# TopLevel.net
KiCad netlist of a schematic drawn in Altium Designer
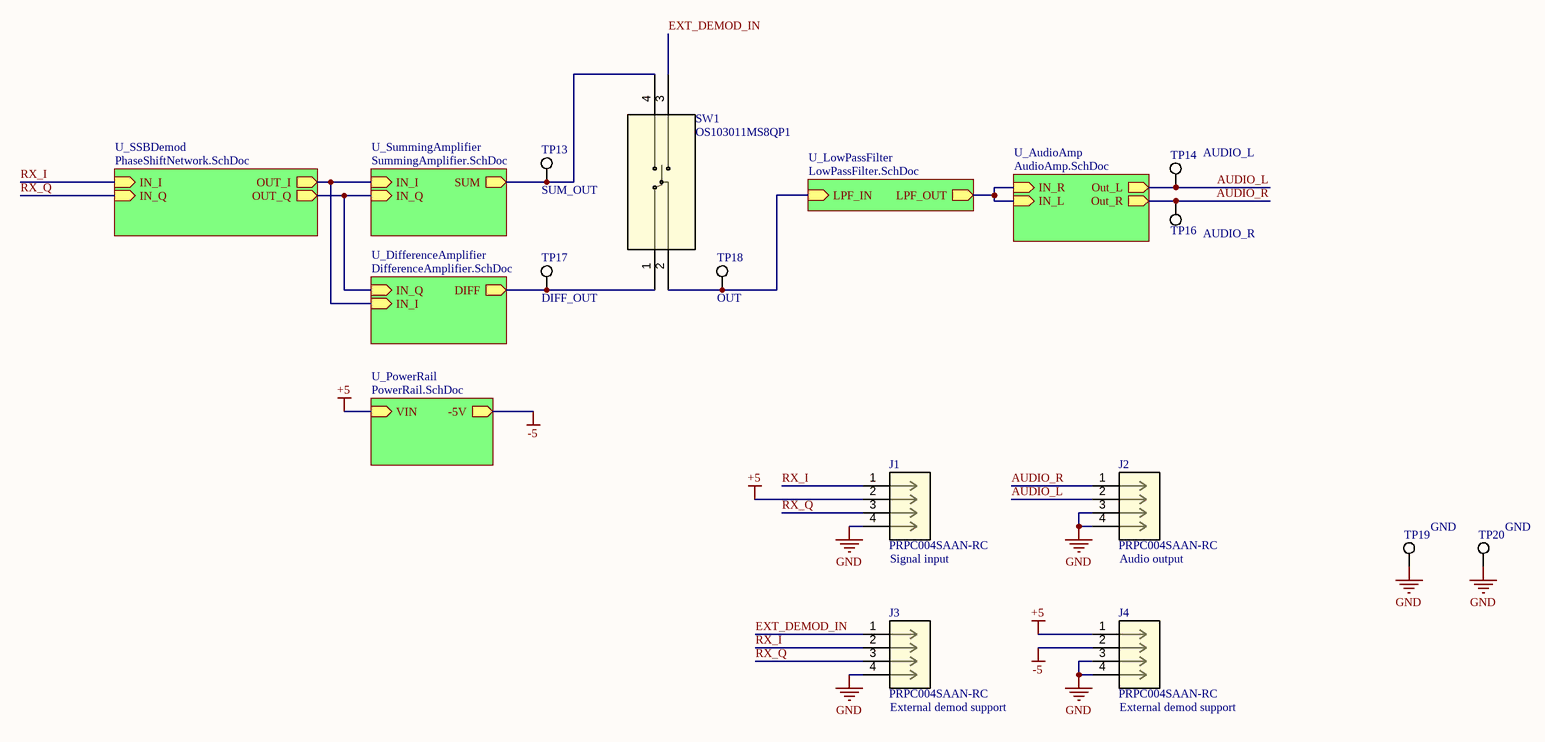
[diagram p0: TopLevel.SchDoc]

(export (version "E")
  (design (tool "Eeschema 10.0.6"))
  (components
    (comp (ref "J1")
      (value "PRPC004SAAN-RC")
      (footprint "CONN4_PRPC004_SUL")
      (description "No Description Available")
      (libsource (lib "PRPC004SAAN-RC") (part "PRPC004SAAN-RC"))
    )
    (comp (ref "J2")
      (value "PRPC004SAAN-RC")
      (footprint "CONN4_PRPC004_SUL")
      (description "No Description Available")
      (libsource (lib "PRPC004SAAN-RC") (part "PRPC004SAAN-RC"))
    )
    (comp (ref "J3")
      (value "PRPC004SAAN-RC")
      (footprint "CONN4_PRPC004_SUL")
      (description "No Description Available")
      (libsource (lib "PRPC004SAAN-RC") (part "PRPC004SAAN-RC"))
    )
    (comp (ref "J4")
      (value "PRPC004SAAN-RC")
      (footprint "CONN4_PRPC004_SUL")
      (description "No Description Available")
      (libsource (lib "PRPC004SAAN-RC") (part "PRPC004SAAN-RC"))
    )
    (comp (ref "SW1")
      (value "OS103011MS8QP1")
      (footprint "DIP4_SP3T-TOP_4P3X8P6_CNK")
      (description "No Description Available")
      (libsource (lib "OS103011MS8QP1") (part "OS103011MS8QP1"))
    )
    (comp (ref "TP13")
      (value "SUM_OUT")
      (footprint "KSTN-5019_V")
      (description "Test Point, 1 Position SMD, RoHS, Tape and Reel")
      (libsource (lib "Altium Content Vault") (part "TESTPOINT_WHITE"))
    )
    (comp (ref "TP14")
      (value "AUDIO_L")
      (footprint "KSTN-5019_V")
      (description "Test Point, 1 Position SMD, RoHS, Tape and Reel")
      (libsource (lib "Altium Content Vault") (part "TESTPOINT_WHITE"))
    )
    (comp (ref "TP16")
      (value "AUDIO_R")
      (footprint "KSTN-5019_V")
      (description "Test Point, 1 Position SMD, RoHS, Tape and Reel")
      (libsource (lib "Altium Content Vault") (part "TESTPOINT_WHITE"))
    )
    (comp (ref "TP17")
      (value "DIFF_OUT")
      (footprint "KSTN-5019_V")
      (description "Test Point, 1 Position SMD, RoHS, Tape and Reel")
      (libsource (lib "Altium Content Vault") (part "TESTPOINT_WHITE"))
    )
    (comp (ref "TP18")
      (value "OUT")
      (footprint "KSTN-5019_V")
      (description "Test Point, 1 Position SMD, RoHS, Tape and Reel")
      (libsource (lib "Altium Content Vault") (part "TESTPOINT_WHITE"))
    )
    (comp (ref "TP19")
      (value "GND")
      (footprint "KSTN-5019_V")
      (description "Test Point, 1 Position SMD, RoHS, Tape and Reel")
      (libsource (lib "Altium Content Vault") (part "TESTPOINT_WHITE"))
    )
    (comp (ref "TP20")
      (value "GND")
      (footprint "KSTN-5019_V")
      (description "Test Point, 1 Position SMD, RoHS, Tape and Reel")
      (libsource (lib "Altium Content Vault") (part "TESTPOINT_WHITE"))
    )
  )
  (nets
    (net (code "1") (name "+5") (class "Default")
      (node (ref "J1") (pin "2") (pinfunction "2_2") (pintype "passive"))
      (node (ref "J4") (pin "1") (pinfunction "1_1") (pintype "passive"))
    )
    (net (code "2") (name "-5") (class "Default")
      (node (ref "J4") (pin "2") (pinfunction "2_2") (pintype "passive"))
    )
    (net (code "3") (name "/AUDIO_L") (class "Default")
      (node (ref "J2") (pin "2") (pinfunction "2_2") (pintype "passive"))
      (node (ref "TP14") (pin "1") (pinfunction "1_1") (pintype "passive"))
    )
    (net (code "4") (name "/AUDIO_R") (class "Default")
      (node (ref "J2") (pin "1") (pinfunction "1_1") (pintype "passive"))
      (node (ref "TP16") (pin "1") (pinfunction "1_1") (pintype "passive"))
    )
    (net (code "5") (name "/DIFF") (class "Default")
      (node (ref "SW1") (pin "1") (pinfunction "1_1") (pintype "passive"))
      (node (ref "TP17") (pin "1") (pinfunction "1_1") (pintype "passive"))
    )
    (net (code "6") (name "/EXT_DEMOD_IN") (class "Default")
      (node (ref "J3") (pin "1") (pinfunction "1_1") (pintype "passive"))
      (node (ref "SW1") (pin "3") (pinfunction "3_3") (pintype "passive"))
    )
    (net (code "7") (name "/LPF_IN") (class "Default")
      (node (ref "SW1") (pin "2") (pinfunction "2_2") (pintype "passive"))
      (node (ref "TP18") (pin "1") (pinfunction "1_1") (pintype "passive"))
    )
    (net (code "11") (name "/RX_I") (class "Default")
      (node (ref "J1") (pin "1") (pinfunction "1_1") (pintype "passive"))
      (node (ref "J3") (pin "2") (pinfunction "2_2") (pintype "passive"))
    )
    (net (code "12") (name "/RX_Q") (class "Default")
      (node (ref "J1") (pin "3") (pinfunction "3_3") (pintype "passive"))
      (node (ref "J3") (pin "3") (pinfunction "3_3") (pintype "passive"))
    )
    (net (code "13") (name "/SUM") (class "Default")
      (node (ref "SW1") (pin "4") (pinfunction "4_4") (pintype "passive"))
      (node (ref "TP13") (pin "1") (pinfunction "1_1") (pintype "passive"))
    )
    (net (code "14") (name "GND") (class "Default")
      (node (ref "J1") (pin "4") (pinfunction "4_4") (pintype "passive"))
      (node (ref "J2") (pin "3") (pinfunction "3_3") (pintype "passive"))
      (node (ref "J2") (pin "4") (pinfunction "4_4") (pintype "passive"))
      (node (ref "J3") (pin "4") (pinfunction "4_4") (pintype "passive"))
      (node (ref "J4") (pin "3") (pinfunction "3_3") (pintype "passive"))
      (node (ref "J4") (pin "4") (pinfunction "4_4") (pintype "passive"))
      (node (ref "TP19") (pin "1") (pinfunction "1_1") (pintype "passive"))
      (node (ref "TP20") (pin "1") (pinfunction "1_1") (pintype "passive"))
    )
  )
)
